# power.net
KiCad netlist of a schematic drawn in Altium Designer
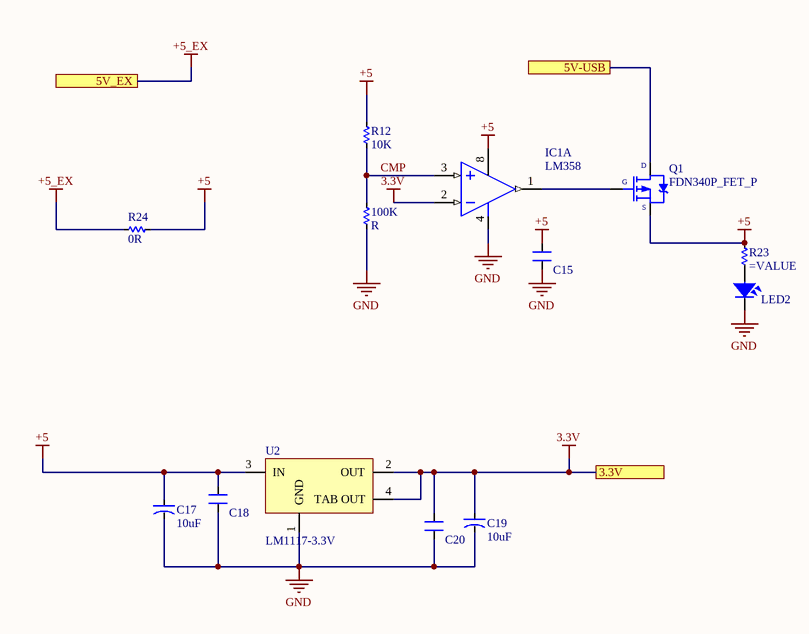
[diagram p0: power.SchDoc]

(export (version "E")
  (design (tool "Eeschema 10.0.6"))
  (components
    (comp (ref "100K") (value "R") (footprint "RES-SMD-0603_BIG") (libsource (lib "nhan") (part "R")))
    (comp (ref "C15") (value "CN") (footprint "CN-SMD-0603_big") (libsource (lib "nhan") (part "CN")))
    (comp (ref "C17")
      (value "10uF")
      (footprint "CAP-ALU-SMD-6.3x7.7x2.2")
      (description "Polarized Capacitor (Axial)")
      (fields (field (name "PUBLISHER") "Altium Limited"))
      (libsource (lib "LIBRARY") (part "CN-ALU-SMD"))
    )
    (comp (ref "C18") (value "CN") (footprint "CN-SMD-0603_big") (libsource (lib "nhan") (part "CN")))
    (comp (ref "C19")
      (value "10uF")
      (footprint "CAP-ALU-SMD-6.3x7.7x2.2")
      (description "Polarized Capacitor (Axial)")
      (fields (field (name "PUBLISHER") "Altium Limited"))
      (libsource (lib "LIBRARY") (part "CN-ALU-SMD"))
    )
    (comp (ref "C20") (value "CN") (footprint "CN-SMD-0603_big") (libsource (lib "nhan") (part "CN")))
    (comp (ref "IC1")
      (value "LM358")
      (footprint "SO8")
      (description "Low-Power Dual Operational Amplifier")
      (libsource (lib "LIBRARY") (part "LM358"))
    )
    (comp (ref "LED2") (value "LED") (footprint "LED-RED-0805") (libsource (lib "LIBRARY") (part "LED SMD")))
    (comp (ref "Q1")
      (value "FDN340P_FET_P")
      (footprint "SOT23F")
      (description "P-Channel, 20V, 2A")
      (libsource (lib "nhan") (part "FDN340P_FET_P"))
    )
    (comp (ref "R12") (value "10K") (footprint "RES-SMD-0603_BIG") (libsource (lib "nhan") (part "R")))
    (comp (ref "R23") (value "~") (footprint "RES-SMD-0603_BIG") (libsource (lib "nhan") (part "R")))
    (comp (ref "R24") (value "0R") (footprint "RES-SMD-0603_BIG") (libsource (lib "nhan") (part "R")))
    (comp (ref "U2")
      (value "LM1117-3.3V")
      (footprint "SOT223")
      (description "800mA Low-Dropout Linear Regulator")
      (fields (field (name "CREATOR") "Nguyen Ba Bien"))
      (libsource (lib "nhan") (part "LM1117"))
    )
  )
  (nets
    (net (code "1") (name "+5") (class "Default")
      (node (ref "C15") (pin "2") (pinfunction "2_2") (pintype "passive"))
      (node (ref "C17") (pin "1") (pinfunction "1_1") (pintype "passive"))
      (node (ref "C18") (pin "2") (pinfunction "2_2") (pintype "passive"))
      (node (ref "IC1") (pin "8") (pinfunction "+V_8") (pintype "passive"))
      (node (ref "Q1") (pin "2") (pinfunction "S_2") (pintype "passive"))
      (node (ref "R12") (pin "1") (pinfunction "1_1") (pintype "passive"))
      (node (ref "R23") (pin "1") (pinfunction "1_1") (pintype "passive"))
      (node (ref "R24") (pin "2") (pinfunction "2_2") (pintype "passive"))
      (node (ref "U2") (pin "3") (pinfunction "IN_3") (pintype "passive"))
    )
    (net (code "2") (name "+5_EX") (class "Default")
      (node (ref "R24") (pin "1") (pinfunction "1_1") (pintype "passive"))
    )
    (net (code "3") (name "/5V-USB") (class "Default")
      (node (ref "Q1") (pin "3") (pinfunction "D_3") (pintype "passive"))
    )
    (net (code "4") (name "/CMP") (class "Default")
      (node (ref "100K") (pin "1") (pinfunction "1_1") (pintype "passive"))
      (node (ref "IC1") (pin "3") (pinfunction "IN+_3") (pintype "input"))
      (node (ref "R12") (pin "2") (pinfunction "2_2") (pintype "passive"))
    )
    (net (code "5") (name "3.3V") (class "Default")
      (node (ref "C19") (pin "1") (pinfunction "1_1") (pintype "passive"))
      (node (ref "C20") (pin "2") (pinfunction "2_2") (pintype "passive"))
      (node (ref "IC1") (pin "2") (pinfunction "IN-_2") (pintype "input"))
      (node (ref "U2") (pin "2") (pinfunction "OUT_2") (pintype "passive"))
      (node (ref "U2") (pin "4") (pinfunction "TAB_OUT_4") (pintype "passive"))
    )
    (net (code "6") (name "GND") (class "Default")
      (node (ref "100K") (pin "2") (pinfunction "2_2") (pintype "passive"))
      (node (ref "C15") (pin "1") (pinfunction "1_1") (pintype "passive"))
      (node (ref "C17") (pin "2") (pinfunction "2_2") (pintype "passive"))
      (node (ref "C18") (pin "1") (pinfunction "1_1") (pintype "passive"))
      (node (ref "C19") (pin "2") (pinfunction "2_2") (pintype "passive"))
      (node (ref "C20") (pin "1") (pinfunction "1_1") (pintype "passive"))
      (node (ref "IC1") (pin "4") (pinfunction "-V_4") (pintype "passive"))
      (node (ref "LED2") (pin "2") (pinfunction "2_2") (pintype "passive"))
      (node (ref "U2") (pin "1") (pinfunction "GND_1") (pintype "passive"))
    )
    (net (code "7") (name "Net-(IC1A-OUT)") (class "Default")
      (node (ref "IC1") (pin "1") (pinfunction "OUT_1") (pintype "output"))
      (node (ref "Q1") (pin "1") (pinfunction "G_1") (pintype "passive"))
    )
    (net (code "8") (name "Net-(LED2-Pad1)") (class "Default")
      (node (ref "LED2") (pin "1") (pinfunction "1_1") (pintype "passive"))
      (node (ref "R23") (pin "2") (pinfunction "2_2") (pintype "passive"))
    )
  )
)
